# pci-reles.net
KiCad netlist of a schematic drawn in Altium Designer
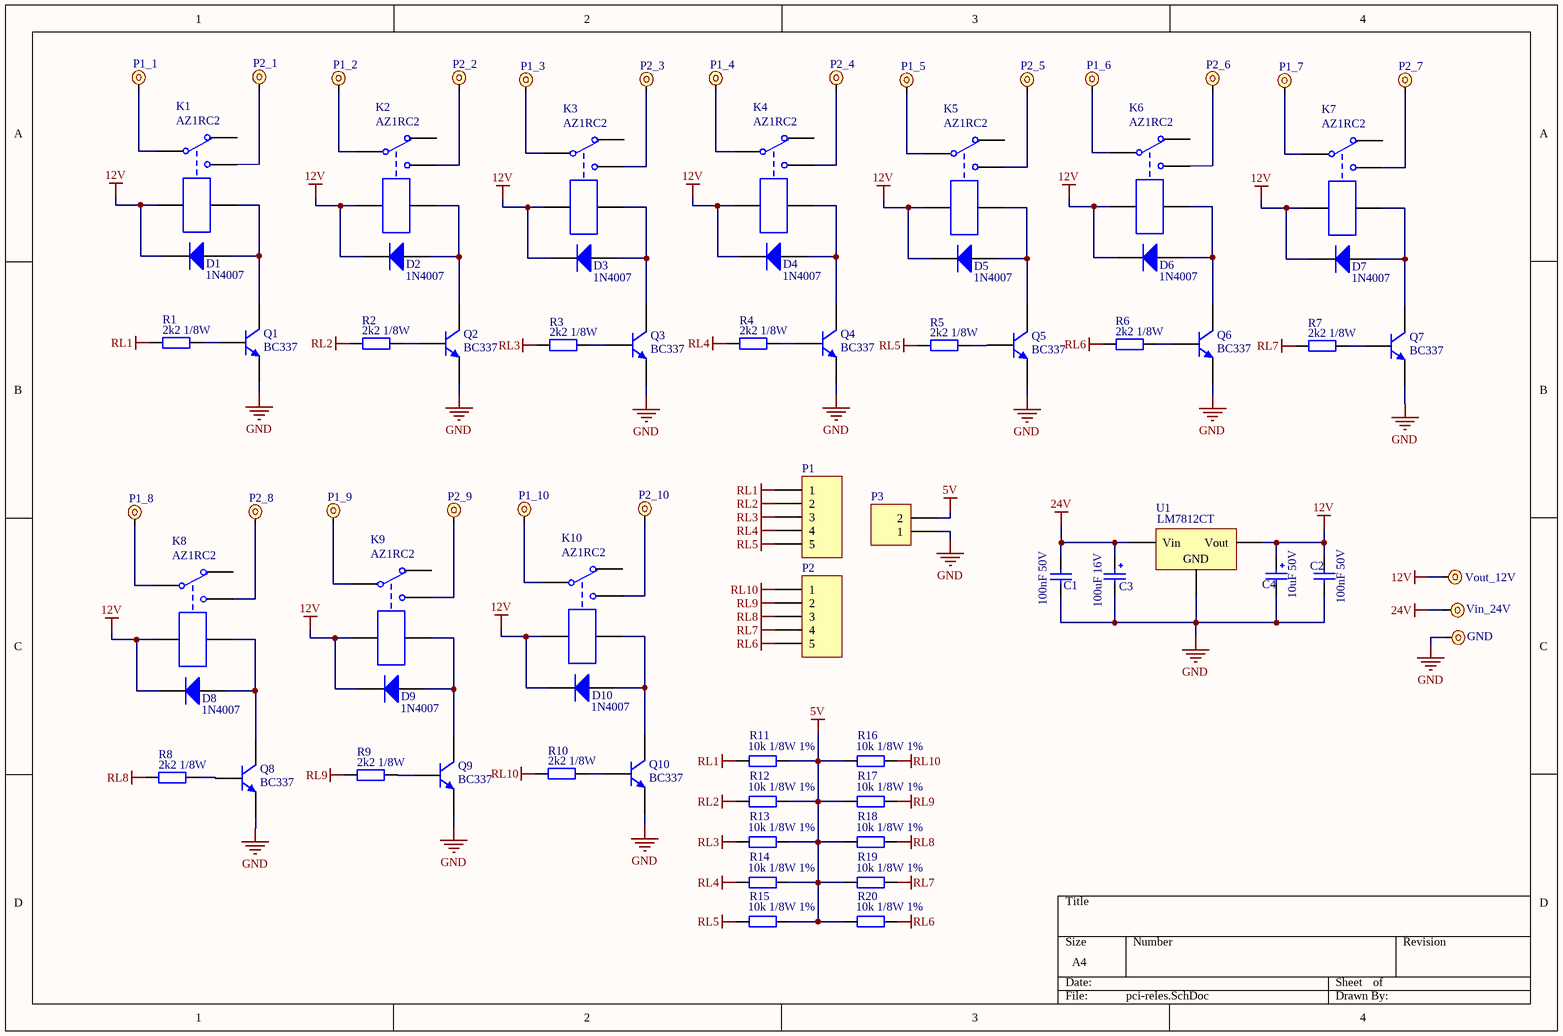
[diagram p0: pci-reles.SchDoc]

(export (version "E")
  (design (tool "Eeschema 10.0.6"))
  (components
    (comp (ref "C1")
      (value "100nF 50V")
      (footprint "Lib PTH:CAP CER 6 x 3 x 5")
      (description "CAP CER 0.1UF 50V Y5V RADIAL")
      (fields
        (field (name "MANUFACTURER") "AVX Corporation")
        (field (name "MANUFACTURER PART NUMBER") "5ZH104ZOCAM")
      )
      (libsource (lib "Lib PTH") (part "Cap Cerâmico 100nF 50V"))
    )
    (comp (ref "C2")
      (value "100nF 50V")
      (footprint "Lib PTH:CAP CER 6 x 3 x 5")
      (description "CAP CER 0.1UF 50V Y5V RADIAL")
      (fields
        (field (name "MANUFACTURER") "AVX Corporation")
        (field (name "MANUFACTURER PART NUMBER") "5ZH104ZOCAM")
      )
      (libsource (lib "Lib PTH") (part "Cap Cerâmico 100nF 50V"))
    )
    (comp (ref "C3")
      (value "100uF 16V")
      (footprint "Lib PTH:CAP ELE 5 x 11 x 2")
      (description "CAP ALUM 100UF 20% 16V RADIAL")
      (fields
        (field (name "MANUFACTURER") "Nichicon")
        (field (name "MANUFACTURER PART NUMBER") "UFW1C101MDD1TD")
      )
      (libsource (lib "Lib PTH") (part "Cap Eletrolitico 100uF/16V"))
    )
    (comp (ref "C4")
      (value "10uF 50V")
      (footprint "Lib PTH:CAP ELE 5 x 11 x 2")
      (description "CAP ALUM 10UF 20% 400V RADIAL")
      (fields
        (field (name "MANUFACTURER") "Nichicon")
        (field (name "MANUFACTURER PART NUMBER") "UVY2G100MPD")
      )
      (libsource (lib "Lib PTH") (part "Cap Eletrolitico 10uF 400V"))
    )
    (comp (ref "D1")
      (value "1N4007")
      (footprint "Lib PTH:DO-41")
      (description "DIODE GEN PURP 1KV 1A DO41")
      (fields
        (field (name "MANUFACTURER") "Diodes Incorporated")
        (field (name "MANUFACTURER PART NUMBER") "1N4007G-T")
      )
      (libsource (lib "Lib PTH") (part "Diodo 1N4007"))
    )
    (comp (ref "D2")
      (value "1N4007")
      (footprint "Lib PTH:DO-41")
      (description "DIODE GEN PURP 1KV 1A DO41")
      (fields
        (field (name "MANUFACTURER") "Diodes Incorporated")
        (field (name "MANUFACTURER PART NUMBER") "1N4007G-T")
      )
      (libsource (lib "Lib PTH") (part "Diodo 1N4007"))
    )
    (comp (ref "D3")
      (value "1N4007")
      (footprint "Lib PTH:DO-41")
      (description "DIODE GEN PURP 1KV 1A DO41")
      (fields
        (field (name "MANUFACTURER") "Diodes Incorporated")
        (field (name "MANUFACTURER PART NUMBER") "1N4007G-T")
      )
      (libsource (lib "Lib PTH") (part "Diodo 1N4007"))
    )
    (comp (ref "D4")
      (value "1N4007")
      (footprint "Lib PTH:DO-41")
      (description "DIODE GEN PURP 1KV 1A DO41")
      (fields
        (field (name "MANUFACTURER") "Diodes Incorporated")
        (field (name "MANUFACTURER PART NUMBER") "1N4007G-T")
      )
      (libsource (lib "Lib PTH") (part "Diodo 1N4007"))
    )
    (comp (ref "D5")
      (value "1N4007")
      (footprint "Lib PTH:DO-41")
      (description "DIODE GEN PURP 1KV 1A DO41")
      (fields
        (field (name "MANUFACTURER") "Diodes Incorporated")
        (field (name "MANUFACTURER PART NUMBER") "1N4007G-T")
      )
      (libsource (lib "Lib PTH") (part "Diodo 1N4007"))
    )
    (comp (ref "D6")
      (value "1N4007")
      (footprint "Lib PTH:DO-41")
      (description "DIODE GEN PURP 1KV 1A DO41")
      (fields
        (field (name "MANUFACTURER") "Diodes Incorporated")
        (field (name "MANUFACTURER PART NUMBER") "1N4007G-T")
      )
      (libsource (lib "Lib PTH") (part "Diodo 1N4007"))
    )
    (comp (ref "D7")
      (value "1N4007")
      (footprint "Lib PTH:DO-41")
      (description "DIODE GEN PURP 1KV 1A DO41")
      (fields
        (field (name "MANUFACTURER") "Diodes Incorporated")
        (field (name "MANUFACTURER PART NUMBER") "1N4007G-T")
      )
      (libsource (lib "Lib PTH") (part "Diodo 1N4007"))
    )
    (comp (ref "D8")
      (value "1N4007")
      (footprint "Lib PTH:DO-41")
      (description "DIODE GEN PURP 1KV 1A DO41")
      (fields
        (field (name "MANUFACTURER") "Diodes Incorporated")
        (field (name "MANUFACTURER PART NUMBER") "1N4007G-T")
      )
      (libsource (lib "Lib PTH") (part "Diodo 1N4007"))
    )
    (comp (ref "D9")
      (value "1N4007")
      (footprint "Lib PTH:DO-41")
      (description "DIODE GEN PURP 1KV 1A DO41")
      (fields
        (field (name "MANUFACTURER") "Diodes Incorporated")
        (field (name "MANUFACTURER PART NUMBER") "1N4007G-T")
      )
      (libsource (lib "Lib PTH") (part "Diodo 1N4007"))
    )
    (comp (ref "D10")
      (value "1N4007")
      (footprint "Lib PTH:DO-41")
      (description "DIODE GEN PURP 1KV 1A DO41")
      (fields
        (field (name "MANUFACTURER") "Diodes Incorporated")
        (field (name "MANUFACTURER PART NUMBER") "1N4007G-T")
      )
      (libsource (lib "Lib PTH") (part "Diodo 1N4007"))
    )
    (comp (ref "GND")
      (value "PAD 1.5x3mm")
      (footprint "Lib PTH:PAD 1.5x3mm")
      (description "PAD")
      (libsource (lib "Lib PTH") (part "PAD 1.5x3mm"))
    )
    (comp (ref "K1")
      (value "AZ1RC2")
      (footprint "Lib PTH:RELE SPDT")
      (description "RELAY GEN PURPOSE SPDT 10A 12V")
      (fields (field (name "MANUFACTURER") "Metaltex"))
      (libsource (lib "Lib PTH") (part "Rele AZ1RC2"))
    )
    (comp (ref "K2")
      (value "AZ1RC2")
      (footprint "Lib PTH:RELE SPDT")
      (description "RELAY GEN PURPOSE SPDT 10A 12V")
      (fields (field (name "MANUFACTURER") "Metaltex"))
      (libsource (lib "Lib PTH") (part "Rele AZ1RC2"))
    )
    (comp (ref "K3")
      (value "AZ1RC2")
      (footprint "Lib PTH:RELE SPDT")
      (description "RELAY GEN PURPOSE SPDT 10A 12V")
      (fields (field (name "MANUFACTURER") "Metaltex"))
      (libsource (lib "Lib PTH") (part "Rele AZ1RC2"))
    )
    (comp (ref "K4")
      (value "AZ1RC2")
      (footprint "Lib PTH:RELE SPDT")
      (description "RELAY GEN PURPOSE SPDT 10A 12V")
      (fields (field (name "MANUFACTURER") "Metaltex"))
      (libsource (lib "Lib PTH") (part "Rele AZ1RC2"))
    )
    (comp (ref "K5")
      (value "AZ1RC2")
      (footprint "Lib PTH:RELE SPDT")
      (description "RELAY GEN PURPOSE SPDT 10A 12V")
      (fields (field (name "MANUFACTURER") "Metaltex"))
      (libsource (lib "Lib PTH") (part "Rele AZ1RC2"))
    )
    (comp (ref "K6")
      (value "AZ1RC2")
      (footprint "Lib PTH:RELE SPDT")
      (description "RELAY GEN PURPOSE SPDT 10A 12V")
      (fields (field (name "MANUFACTURER") "Metaltex"))
      (libsource (lib "Lib PTH") (part "Rele AZ1RC2"))
    )
    (comp (ref "K7")
      (value "AZ1RC2")
      (footprint "Lib PTH:RELE SPDT")
      (description "RELAY GEN PURPOSE SPDT 10A 12V")
      (fields (field (name "MANUFACTURER") "Metaltex"))
      (libsource (lib "Lib PTH") (part "Rele AZ1RC2"))
    )
    (comp (ref "K8")
      (value "AZ1RC2")
      (footprint "Lib PTH:RELE SPDT")
      (description "RELAY GEN PURPOSE SPDT 10A 12V")
      (fields (field (name "MANUFACTURER") "Metaltex"))
      (libsource (lib "Lib PTH") (part "Rele AZ1RC2"))
    )
    (comp (ref "K9")
      (value "AZ1RC2")
      (footprint "Lib PTH:RELE SPDT")
      (description "RELAY GEN PURPOSE SPDT 10A 12V")
      (fields (field (name "MANUFACTURER") "Metaltex"))
      (libsource (lib "Lib PTH") (part "Rele AZ1RC2"))
    )
    (comp (ref "K10")
      (value "AZ1RC2")
      (footprint "Lib PTH:RELE SPDT")
      (description "RELAY GEN PURPOSE SPDT 10A 12V")
      (fields (field (name "MANUFACTURER") "Metaltex"))
      (libsource (lib "Lib PTH") (part "Rele AZ1RC2"))
    )
    (comp (ref "P1")
      (value "Barra de Pinos RL")
      (footprint "Lib PTH:HEADER 5X2.54MM")
      (description "CONN HEADER 5 POS 2.54")
      (fields (field (name "MANUFACTURER") "Metaltex") (field (name "MANUFACTURER PART NUMBER") "BPSC-5"))
      (libsource (lib "Lib PTH") (part "Barra de pinos simples 180°, 5 pinos"))
    )
    (comp (ref "P1_1")
      (value "PAD 1.5x3mm")
      (footprint "Lib PTH:PAD 1.5x3mm")
      (description "PAD")
      (libsource (lib "Lib PTH") (part "PAD 1.5x3mm"))
    )
    (comp (ref "P1_2")
      (value "PAD 1.5x3mm")
      (footprint "Lib PTH:PAD 1.5x3mm")
      (description "PAD")
      (libsource (lib "Lib PTH") (part "PAD 1.5x3mm"))
    )
    (comp (ref "P1_3")
      (value "PAD 1.5x3mm")
      (footprint "Lib PTH:PAD 1.5x3mm")
      (description "PAD")
      (libsource (lib "Lib PTH") (part "PAD 1.5x3mm"))
    )
    (comp (ref "P1_4")
      (value "PAD 1.5x3mm")
      (footprint "Lib PTH:PAD 1.5x3mm")
      (description "PAD")
      (libsource (lib "Lib PTH") (part "PAD 1.5x3mm"))
    )
    (comp (ref "P1_5")
      (value "PAD 1.5x3mm")
      (footprint "Lib PTH:PAD 1.5x3mm")
      (description "PAD")
      (libsource (lib "Lib PTH") (part "PAD 1.5x3mm"))
    )
    (comp (ref "P1_6")
      (value "PAD 1.5x3mm")
      (footprint "Lib PTH:PAD 1.5x3mm")
      (description "PAD")
      (libsource (lib "Lib PTH") (part "PAD 1.5x3mm"))
    )
    (comp (ref "P1_7")
      (value "PAD 1.5x3mm")
      (footprint "Lib PTH:PAD 1.5x3mm")
      (description "PAD")
      (libsource (lib "Lib PTH") (part "PAD 1.5x3mm"))
    )
    (comp (ref "P1_8")
      (value "PAD 1.5x3mm")
      (footprint "Lib PTH:PAD 1.5x3mm")
      (description "PAD")
      (libsource (lib "Lib PTH") (part "PAD 1.5x3mm"))
    )
    (comp (ref "P1_9")
      (value "PAD 1.5x3mm")
      (footprint "Lib PTH:PAD 1.5x3mm")
      (description "PAD")
      (libsource (lib "Lib PTH") (part "PAD 1.5x3mm"))
    )
    (comp (ref "P1_10")
      (value "PAD 1.5x3mm")
      (footprint "Lib PTH:PAD 1.5x3mm")
      (description "PAD")
      (libsource (lib "Lib PTH") (part "PAD 1.5x3mm"))
    )
    (comp (ref "P2")
      (value "Barra de Pinos RL")
      (footprint "Lib PTH:HEADER 5X2.54MM")
      (description "CONN HEADER 5 POS 2.54")
      (fields (field (name "MANUFACTURER") "Metaltex") (field (name "MANUFACTURER PART NUMBER") "BPSC-5"))
      (libsource (lib "Lib PTH") (part "Barra de pinos simples 180°, 5 pinos"))
    )
    (comp (ref "P2_1")
      (value "PAD 1.5x3mm")
      (footprint "Lib PTH:PAD 1.5x3mm")
      (description "PAD")
      (libsource (lib "Lib PTH") (part "PAD 1.5x3mm"))
    )
    (comp (ref "P2_2")
      (value "PAD 1.5x3mm")
      (footprint "Lib PTH:PAD 1.5x3mm")
      (description "PAD")
      (libsource (lib "Lib PTH") (part "PAD 1.5x3mm"))
    )
    (comp (ref "P2_3")
      (value "PAD 1.5x3mm")
      (footprint "Lib PTH:PAD 1.5x3mm")
      (description "PAD")
      (libsource (lib "Lib PTH") (part "PAD 1.5x3mm"))
    )
    (comp (ref "P2_4")
      (value "PAD 1.5x3mm")
      (footprint "Lib PTH:PAD 1.5x3mm")
      (description "PAD")
      (libsource (lib "Lib PTH") (part "PAD 1.5x3mm"))
    )
    (comp (ref "P2_5")
      (value "PAD 1.5x3mm")
      (footprint "Lib PTH:PAD 1.5x3mm")
      (description "PAD")
      (libsource (lib "Lib PTH") (part "PAD 1.5x3mm"))
    )
    (comp (ref "P2_6")
      (value "PAD 1.5x3mm")
      (footprint "Lib PTH:PAD 1.5x3mm")
      (description "PAD")
      (libsource (lib "Lib PTH") (part "PAD 1.5x3mm"))
    )
    (comp (ref "P2_7")
      (value "PAD 1.5x3mm")
      (footprint "Lib PTH:PAD 1.5x3mm")
      (description "PAD")
      (libsource (lib "Lib PTH") (part "PAD 1.5x3mm"))
    )
    (comp (ref "P2_8")
      (value "PAD 1.5x3mm")
      (footprint "Lib PTH:PAD 1.5x3mm")
      (description "PAD")
      (libsource (lib "Lib PTH") (part "PAD 1.5x3mm"))
    )
    (comp (ref "P2_9")
      (value "PAD 1.5x3mm")
      (footprint "Lib PTH:PAD 1.5x3mm")
      (description "PAD")
      (libsource (lib "Lib PTH") (part "PAD 1.5x3mm"))
    )
    (comp (ref "P2_10")
      (value "PAD 1.5x3mm")
      (footprint "Lib PTH:PAD 1.5x3mm")
      (description "PAD")
      (libsource (lib "Lib PTH") (part "PAD 1.5x3mm"))
    )
    (comp (ref "P3")
      (value "Barra de Pinos VCC/GND")
      (footprint "Lib PTH:HEADER 2X2.54MM")
      (description "CONN HEADER 2 POS 2.54")
      (fields (field (name "MANUFACTURER") "Metaltex") (field (name "MANUFACTURER PART NUMBER") "BPSC-2"))
      (libsource (lib "Lib PTH") (part "Barra de pinos simples 180°, 2 pinos"))
    )
    (comp (ref "Q1")
      (value "BC337")
      (footprint "Lib PTH:TO-92A")
      (description "TRANS NPN 45V 0.8A TO-92")
      (fields
        (field (name "MANUFACTURER") "ON Semiconductor")
        (field (name "MANUFACTURER PART NUMBER") "BC33740TA")
      )
      (libsource (lib "Lib PTH") (part "Transistor NPN BC337-40"))
    )
    (comp (ref "Q2")
      (value "BC337")
      (footprint "Lib PTH:TO-92A")
      (description "TRANS NPN 45V 0.8A TO-92")
      (fields
        (field (name "MANUFACTURER") "ON Semiconductor")
        (field (name "MANUFACTURER PART NUMBER") "BC33740TA")
      )
      (libsource (lib "Lib PTH") (part "Transistor NPN BC337-40"))
    )
    (comp (ref "Q3")
      (value "BC337")
      (footprint "Lib PTH:TO-92A")
      (description "TRANS NPN 45V 0.8A TO-92")
      (fields
        (field (name "MANUFACTURER") "ON Semiconductor")
        (field (name "MANUFACTURER PART NUMBER") "BC33740TA")
      )
      (libsource (lib "Lib PTH") (part "Transistor NPN BC337-40"))
    )
    (comp (ref "Q4")
      (value "BC337")
      (footprint "Lib PTH:TO-92A")
      (description "TRANS NPN 45V 0.8A TO-92")
      (fields
        (field (name "MANUFACTURER") "ON Semiconductor")
        (field (name "MANUFACTURER PART NUMBER") "BC33740TA")
      )
      (libsource (lib "Lib PTH") (part "Transistor NPN BC337-40"))
    )
    (comp (ref "Q5")
      (value "BC337")
      (footprint "Lib PTH:TO-92A")
      (description "TRANS NPN 45V 0.8A TO-92")
      (fields
        (field (name "MANUFACTURER") "ON Semiconductor")
        (field (name "MANUFACTURER PART NUMBER") "BC33740TA")
      )
      (libsource (lib "Lib PTH") (part "Transistor NPN BC337-40"))
    )
    (comp (ref "Q6")
      (value "BC337")
      (footprint "Lib PTH:TO-92A")
      (description "TRANS NPN 45V 0.8A TO-92")
      (fields
        (field (name "MANUFACTURER") "ON Semiconductor")
        (field (name "MANUFACTURER PART NUMBER") "BC33740TA")
      )
      (libsource (lib "Lib PTH") (part "Transistor NPN BC337-40"))
    )
    (comp (ref "Q7")
      (value "BC337")
      (footprint "Lib PTH:TO-92A")
      (description "TRANS NPN 45V 0.8A TO-92")
      (fields
        (field (name "MANUFACTURER") "ON Semiconductor")
        (field (name "MANUFACTURER PART NUMBER") "BC33740TA")
      )
      (libsource (lib "Lib PTH") (part "Transistor NPN BC337-40"))
    )
    (comp (ref "Q8")
      (value "BC337")
      (footprint "Lib PTH:TO-92A")
      (description "TRANS NPN 45V 0.8A TO-92")
      (fields
        (field (name "MANUFACTURER") "ON Semiconductor")
        (field (name "MANUFACTURER PART NUMBER") "BC33740TA")
      )
      (libsource (lib "Lib PTH") (part "Transistor NPN BC337-40"))
    )
    (comp (ref "Q9")
      (value "BC337")
      (footprint "Lib PTH:TO-92A")
      (description "TRANS NPN 45V 0.8A TO-92")
      (fields
        (field (name "MANUFACTURER") "ON Semiconductor")
        (field (name "MANUFACTURER PART NUMBER") "BC33740TA")
      )
      (libsource (lib "Lib PTH") (part "Transistor NPN BC337-40"))
    )
    (comp (ref "Q10")
      (value "BC337")
      (footprint "Lib PTH:TO-92A")
      (description "TRANS NPN 45V 0.8A TO-92")
      (fields
        (field (name "MANUFACTURER") "ON Semiconductor")
        (field (name "MANUFACTURER PART NUMBER") "BC33740TA")
      )
      (libsource (lib "Lib PTH") (part "Transistor NPN BC337-40"))
    )
    (comp (ref "R1")
      (value "2k2 1/8W")
      (footprint "Lib PTH:RES CR16")
      (description "RES 2K2 OHM 1/8W 5% AXIAL")
      (fields
        (field (name "MANUFACTURER") "Stackpole Electronics Inc.")
        (field (name "MANUFACTURER PART NUMBER") "CF18JT2K20")
      )
      (libsource (lib "Lib PTH") (part "Res 2k2 1/8W 5% CR16"))
    )
    (comp (ref "R2")
      (value "2k2 1/8W")
      (footprint "Lib PTH:RES CR16")
      (description "RES 2K2 OHM 1/8W 5% AXIAL")
      (fields
        (field (name "MANUFACTURER") "Stackpole Electronics Inc.")
        (field (name "MANUFACTURER PART NUMBER") "CF18JT2K20")
      )
      (libsource (lib "Lib PTH") (part "Res 2k2 1/8W 5% CR16"))
    )
    (comp (ref "R3")
      (value "2k2 1/8W")
      (footprint "Lib PTH:RES CR16")
      (description "RES 2K2 OHM 1/8W 5% AXIAL")
      (fields
        (field (name "MANUFACTURER") "Stackpole Electronics Inc.")
        (field (name "MANUFACTURER PART NUMBER") "CF18JT2K20")
      )
      (libsource (lib "Lib PTH") (part "Res 2k2 1/8W 5% CR16"))
    )
    (comp (ref "R4")
      (value "2k2 1/8W")
      (footprint "Lib PTH:RES CR16")
      (description "RES 2K2 OHM 1/8W 5% AXIAL")
      (fields
        (field (name "MANUFACTURER") "Stackpole Electronics Inc.")
        (field (name "MANUFACTURER PART NUMBER") "CF18JT2K20")
      )
      (libsource (lib "Lib PTH") (part "Res 2k2 1/8W 5% CR16"))
    )
    (comp (ref "R5")
      (value "2k2 1/8W")
      (footprint "Lib PTH:RES CR16")
      (description "RES 2K2 OHM 1/8W 5% AXIAL")
      (fields
        (field (name "MANUFACTURER") "Stackpole Electronics Inc.")
        (field (name "MANUFACTURER PART NUMBER") "CF18JT2K20")
      )
      (libsource (lib "Lib PTH") (part "Res 2k2 1/8W 5% CR16"))
    )
    (comp (ref "R6")
      (value "2k2 1/8W")
      (footprint "Lib PTH:RES CR16")
      (description "RES 2K2 OHM 1/8W 5% AXIAL")
      (fields
        (field (name "MANUFACTURER") "Stackpole Electronics Inc.")
        (field (name "MANUFACTURER PART NUMBER") "CF18JT2K20")
      )
      (libsource (lib "Lib PTH") (part "Res 2k2 1/8W 5% CR16"))
    )
    (comp (ref "R7")
      (value "2k2 1/8W")
      (footprint "Lib PTH:RES CR16")
      (description "RES 2K2 OHM 1/8W 5% AXIAL")
      (fields
        (field (name "MANUFACTURER") "Stackpole Electronics Inc.")
        (field (name "MANUFACTURER PART NUMBER") "CF18JT2K20")
      )
      (libsource (lib "Lib PTH") (part "Res 2k2 1/8W 5% CR16"))
    )
    (comp (ref "R8")
      (value "2k2 1/8W")
      (footprint "Lib PTH:RES CR16")
      (description "RES 2K2 OHM 1/8W 5% AXIAL")
      (fields
        (field (name "MANUFACTURER") "Stackpole Electronics Inc.")
        (field (name "MANUFACTURER PART NUMBER") "CF18JT2K20")
      )
      (libsource (lib "Lib PTH") (part "Res 2k2 1/8W 5% CR16"))
    )
    (comp (ref "R9")
      (value "2k2 1/8W")
      (footprint "Lib PTH:RES CR16")
      (description "RES 2K2 OHM 1/8W 5% AXIAL")
      (fields
        (field (name "MANUFACTURER") "Stackpole Electronics Inc.")
        (field (name "MANUFACTURER PART NUMBER") "CF18JT2K20")
      )
      (libsource (lib "Lib PTH") (part "Res 2k2 1/8W 5% CR16"))
    )
    (comp (ref "R10")
      (value "2k2 1/8W")
      (footprint "Lib PTH:RES CR16")
      (description "RES 2K2 OHM 1/8W 5% AXIAL")
      (fields
        (field (name "MANUFACTURER") "Stackpole Electronics Inc.")
        (field (name "MANUFACTURER PART NUMBER") "CF18JT2K20")
      )
      (libsource (lib "Lib PTH") (part "Res 2k2 1/8W 5% CR16"))
    )
    (comp (ref "R11")
      (value "10k 1/8W 1%")
      (footprint "Lib PTH:RES CR16")
      (description "RES 10K OHM 1/8W 1% AXIAL")
      (fields
        (field (name "MANUFACTURER") "Stackpole Electronics Inc.")
        (field (name "MANUFACTURER PART NUMBER") "RNF18FTD10K0")
      )
      (libsource (lib "Lib PTH") (part "Res 10k 1/8W 1% CR16"))
    )
    (comp (ref "R12")
      (value "10k 1/8W 1%")
      (footprint "Lib PTH:RES CR16")
      (description "RES 10K OHM 1/8W 1% AXIAL")
      (fields
        (field (name "MANUFACTURER") "Stackpole Electronics Inc.")
        (field (name "MANUFACTURER PART NUMBER") "RNF18FTD10K0")
      )
      (libsource (lib "Lib PTH") (part "Res 10k 1/8W 1% CR16"))
    )
    (comp (ref "R13")
      (value "10k 1/8W 1%")
      (footprint "Lib PTH:RES CR16")
      (description "RES 10K OHM 1/8W 1% AXIAL")
      (fields
        (field (name "MANUFACTURER") "Stackpole Electronics Inc.")
        (field (name "MANUFACTURER PART NUMBER") "RNF18FTD10K0")
      )
      (libsource (lib "Lib PTH") (part "Res 10k 1/8W 1% CR16"))
    )
    (comp (ref "R14")
      (value "10k 1/8W 1%")
      (footprint "Lib PTH:RES CR16")
      (description "RES 10K OHM 1/8W 1% AXIAL")
      (fields
        (field (name "MANUFACTURER") "Stackpole Electronics Inc.")
        (field (name "MANUFACTURER PART NUMBER") "RNF18FTD10K0")
      )
      (libsource (lib "Lib PTH") (part "Res 10k 1/8W 1% CR16"))
    )
    (comp (ref "R15")
      (value "10k 1/8W 1%")
      (footprint "Lib PTH:RES CR16")
      (description "RES 10K OHM 1/8W 1% AXIAL")
      (fields
        (field (name "MANUFACTURER") "Stackpole Electronics Inc.")
        (field (name "MANUFACTURER PART NUMBER") "RNF18FTD10K0")
      )
      (libsource (lib "Lib PTH") (part "Res 10k 1/8W 1% CR16"))
    )
    (comp (ref "R16")
      (value "10k 1/8W 1%")
      (footprint "Lib PTH:RES CR16")
      (description "RES 10K OHM 1/8W 1% AXIAL")
      (fields
        (field (name "MANUFACTURER") "Stackpole Electronics Inc.")
        (field (name "MANUFACTURER PART NUMBER") "RNF18FTD10K0")
      )
      (libsource (lib "Lib PTH") (part "Res 10k 1/8W 1% CR16"))
    )
    (comp (ref "R17")
      (value "10k 1/8W 1%")
      (footprint "Lib PTH:RES CR16")
      (description "RES 10K OHM 1/8W 1% AXIAL")
      (fields
        (field (name "MANUFACTURER") "Stackpole Electronics Inc.")
        (field (name "MANUFACTURER PART NUMBER") "RNF18FTD10K0")
      )
      (libsource (lib "Lib PTH") (part "Res 10k 1/8W 1% CR16"))
    )
    (comp (ref "R18")
      (value "10k 1/8W 1%")
      (footprint "Lib PTH:RES CR16")
      (description "RES 10K OHM 1/8W 1% AXIAL")
      (fields
        (field (name "MANUFACTURER") "Stackpole Electronics Inc.")
        (field (name "MANUFACTURER PART NUMBER") "RNF18FTD10K0")
      )
      (libsource (lib "Lib PTH") (part "Res 10k 1/8W 1% CR16"))
    )
    (comp (ref "R19")
      (value "10k 1/8W 1%")
      (footprint "Lib PTH:RES CR16")
      (description "RES 10K OHM 1/8W 1% AXIAL")
      (fields
        (field (name "MANUFACTURER") "Stackpole Electronics Inc.")
        (field (name "MANUFACTURER PART NUMBER") "RNF18FTD10K0")
      )
      (libsource (lib "Lib PTH") (part "Res 10k 1/8W 1% CR16"))
    )
    (comp (ref "R20")
      (value "10k 1/8W 1%")
      (footprint "Lib PTH:RES CR16")
      (description "RES 10K OHM 1/8W 1% AXIAL")
      (fields
        (field (name "MANUFACTURER") "Stackpole Electronics Inc.")
        (field (name "MANUFACTURER PART NUMBER") "RNF18FTD10K0")
      )
      (libsource (lib "Lib PTH") (part "Res 10k 1/8W 1% CR16"))
    )
    (comp (ref "U1")
      (value "LM7812CT")
      (footprint "Lib PTH:TO220_90")
      (description "IC REG LINEAR 5V 1A TO220-3")
      (fields
        (field (name "MANUFACTURER") "Texas Instruments")
        (field (name "MANUFACTURER PART NUMBER") "LM7805CT/NOPB")
      )
      (libsource (lib "Lib PTH") (part "Regulador de tensão LM7805CT"))
    )
    (comp (ref "Vin_24V")
      (value "PAD 1.5x3mm")
      (footprint "Lib PTH:PAD 1.5x3mm")
      (description "PAD")
      (libsource (lib "Lib PTH") (part "PAD 1.5x3mm"))
    )
    (comp (ref "Vout_12V")
      (value "PAD 1.5x3mm")
      (footprint "Lib PTH:PAD 1.5x3mm")
      (description "PAD")
      (libsource (lib "Lib PTH") (part "PAD 1.5x3mm"))
    )
  )
  (nets
    (net (code "1") (name "5V") (class "Default")
      (node (ref "P3") (pin "2") (pinfunction "2_2") (pintype "passive"))
      (node (ref "R11") (pin "2") (pinfunction "2_2") (pintype "passive"))
      (node (ref "R12") (pin "2") (pinfunction "2_2") (pintype "passive"))
      (node (ref "R13") (pin "2") (pinfunction "2_2") (pintype "passive"))
      (node (ref "R14") (pin "2") (pinfunction "2_2") (pintype "passive"))
      (node (ref "R15") (pin "2") (pinfunction "2_2") (pintype "passive"))
      (node (ref "R16") (pin "1") (pinfunction "1_1") (pintype "passive"))
      (node (ref "R17") (pin "1") (pinfunction "1_1") (pintype "passive"))
      (node (ref "R18") (pin "1") (pinfunction "1_1") (pintype "passive"))
      (node (ref "R19") (pin "1") (pinfunction "1_1") (pintype "passive"))
      (node (ref "R20") (pin "1") (pinfunction "1_1") (pintype "passive"))
    )
    (net (code "2") (name "12V") (class "Default")
      (node (ref "C2") (pin "2") (pinfunction "2_2") (pintype "passive"))
      (node (ref "C4") (pin "1") (pinfunction "1_1") (pintype "passive"))
      (node (ref "D1") (pin "2") (pinfunction "K_2") (pintype "passive"))
      (node (ref "D10") (pin "2") (pinfunction "K_2") (pintype "passive"))
      (node (ref "D2") (pin "2") (pinfunction "K_2") (pintype "passive"))
      (node (ref "D3") (pin "2") (pinfunction "K_2") (pintype "passive"))
      (node (ref "D4") (pin "2") (pinfunction "K_2") (pintype "passive"))
      (node (ref "D5") (pin "2") (pinfunction "K_2") (pintype "passive"))
      (node (ref "D6") (pin "2") (pinfunction "K_2") (pintype "passive"))
      (node (ref "D7") (pin "2") (pinfunction "K_2") (pintype "passive"))
      (node (ref "D8") (pin "2") (pinfunction "K_2") (pintype "passive"))
      (node (ref "D9") (pin "2") (pinfunction "K_2") (pintype "passive"))
      (node (ref "K1") (pin "4") (pinfunction "4_4") (pintype "passive"))
      (node (ref "K10") (pin "4") (pinfunction "4_4") (pintype "passive"))
      (node (ref "K2") (pin "4") (pinfunction "4_4") (pintype "passive"))
      (node (ref "K3") (pin "4") (pinfunction "4_4") (pintype "passive"))
      (node (ref "K4") (pin "4") (pinfunction "4_4") (pintype "passive"))
      (node (ref "K5") (pin "4") (pinfunction "4_4") (pintype "passive"))
      (node (ref "K6") (pin "4") (pinfunction "4_4") (pintype "passive"))
      (node (ref "K7") (pin "4") (pinfunction "4_4") (pintype "passive"))
      (node (ref "K8") (pin "4") (pinfunction "4_4") (pintype "passive"))
      (node (ref "K9") (pin "4") (pinfunction "4_4") (pintype "passive"))
      (node (ref "U1") (pin "3") (pinfunction "Vout_3") (pintype "passive"))
      (node (ref "Vout_12V") (pin "1") (pinfunction "1_1") (pintype "passive"))
    )
    (net (code "3") (name "24V") (class "Default")
      (node (ref "C1") (pin "2") (pinfunction "2_2") (pintype "passive"))
      (node (ref "C3") (pin "1") (pinfunction "1_1") (pintype "passive"))
      (node (ref "U1") (pin "1") (pinfunction "Vin_1") (pintype "passive"))
      (node (ref "Vin_24V") (pin "1") (pinfunction "1_1") (pintype "passive"))
    )
    (net (code "4") (name "GND") (class "Default")
      (node (ref "C1") (pin "1") (pinfunction "1_1") (pintype "passive"))
      (node (ref "C2") (pin "1") (pinfunction "1_1") (pintype "passive"))
      (node (ref "C3") (pin "2") (pinfunction "2_2") (pintype "passive"))
      (node (ref "C4") (pin "2") (pinfunction "2_2") (pintype "passive"))
      (node (ref "GND") (pin "1") (pinfunction "1_1") (pintype "passive"))
      (node (ref "P3") (pin "1") (pinfunction "1_1") (pintype "passive"))
      (node (ref "Q1") (pin "3") (pinfunction "E_3") (pintype "passive"))
      (node (ref "Q10") (pin "3") (pinfunction "E_3") (pintype "passive"))
      (node (ref "Q2") (pin "3") (pinfunction "E_3") (pintype "passive"))
      (node (ref "Q3") (pin "3") (pinfunction "E_3") (pintype "passive"))
      (node (ref "Q4") (pin "3") (pinfunction "E_3") (pintype "passive"))
      (node (ref "Q5") (pin "3") (pinfunction "E_3") (pintype "passive"))
      (node (ref "Q6") (pin "3") (pinfunction "E_3") (pintype "passive"))
      (node (ref "Q7") (pin "3") (pinfunction "E_3") (pintype "passive"))
      (node (ref "Q8") (pin "3") (pinfunction "E_3") (pintype "passive"))
      (node (ref "Q9") (pin "3") (pinfunction "E_3") (pintype "passive"))
      (node (ref "U1") (pin "2") (pinfunction "GND_2") (pintype "passive"))
    )
    (net (code "5") (name "Net-(D1-A)") (class "Default")
      (node (ref "D1") (pin "1") (pinfunction "A_1") (pintype "passive"))
      (node (ref "K1") (pin "5") (pinfunction "5_5") (pintype "passive"))
      (node (ref "Q1") (pin "1") (pinfunction "C_1") (pintype "passive"))
    )
    (net (code "6") (name "Net-(D2-A)") (class "Default")
      (node (ref "D2") (pin "1") (pinfunction "A_1") (pintype "passive"))
      (node (ref "K2") (pin "5") (pinfunction "5_5") (pintype "passive"))
      (node (ref "Q2") (pin "1") (pinfunction "C_1") (pintype "passive"))
    )
    (net (code "7") (name "Net-(D3-A)") (class "Default")
      (node (ref "D3") (pin "1") (pinfunction "A_1") (pintype "passive"))
      (node (ref "K3") (pin "5") (pinfunction "5_5") (pintype "passive"))
      (node (ref "Q3") (pin "1") (pinfunction "C_1") (pintype "passive"))
    )
    (net (code "8") (name "Net-(D4-A)") (class "Default")
      (node (ref "D4") (pin "1") (pinfunction "A_1") (pintype "passive"))
      (node (ref "K4") (pin "5") (pinfunction "5_5") (pintype "passive"))
      (node (ref "Q4") (pin "1") (pinfunction "C_1") (pintype "passive"))
    )
    (net (code "9") (name "Net-(D5-A)") (class "Default")
      (node (ref "D5") (pin "1") (pinfunction "A_1") (pintype "passive"))
      (node (ref "K5") (pin "5") (pinfunction "5_5") (pintype "passive"))
      (node (ref "Q5") (pin "1") (pinfunction "C_1") (pintype "passive"))
    )
    (net (code "10") (name "Net-(D6-A)") (class "Default")
      (node (ref "D6") (pin "1") (pinfunction "A_1") (pintype "passive"))
      (node (ref "K6") (pin "5") (pinfunction "5_5") (pintype "passive"))
      (node (ref "Q6") (pin "1") (pinfunction "C_1") (pintype "passive"))
    )
    (net (code "11") (name "Net-(D7-A)") (class "Default")
      (node (ref "D7") (pin "1") (pinfunction "A_1") (pintype "passive"))
      (node (ref "K7") (pin "5") (pinfunction "5_5") (pintype "passive"))
      (node (ref "Q7") (pin "1") (pinfunction "C_1") (pintype "passive"))
    )
    (net (code "12") (name "Net-(D8-A)") (class "Default")
      (node (ref "D8") (pin "1") (pinfunction "A_1") (pintype "passive"))
      (node (ref "K8") (pin "5") (pinfunction "5_5") (pintype "passive"))
      (node (ref "Q8") (pin "1") (pinfunction "C_1") (pintype "passive"))
    )
    (net (code "13") (name "Net-(D9-A)") (class "Default")
      (node (ref "D9") (pin "1") (pinfunction "A_1") (pintype "passive"))
      (node (ref "K9") (pin "5") (pinfunction "5_5") (pintype "passive"))
      (node (ref "Q9") (pin "1") (pinfunction "C_1") (pintype "passive"))
    )
    (net (code "14") (name "Net-(D10-A)") (class "Default")
      (node (ref "D10") (pin "1") (pinfunction "A_1") (pintype "passive"))
      (node (ref "K10") (pin "5") (pinfunction "5_5") (pintype "passive"))
      (node (ref "Q10") (pin "1") (pinfunction "C_1") (pintype "passive"))
    )
    (net (code "15") (name "Net-(K1-Comum)") (class "Default")
      (node (ref "K1") (pin "1") (pinfunction "Comum_1") (pintype "passive"))
      (node (ref "P1_1") (pin "1") (pinfunction "1_1") (pintype "passive"))
    )
    (net (code "16") (name "Net-(K1-N.A.)") (class "Default")
      (node (ref "K1") (pin "2") (pinfunction "N.A._2") (pintype "passive"))
      (node (ref "P2_1") (pin "1") (pinfunction "1_1") (pintype "passive"))
    )
    (net (code "17") (name "Net-(K2-Comum)") (class "Default")
      (node (ref "K2") (pin "1") (pinfunction "Comum_1") (pintype "passive"))
      (node (ref "P1_2") (pin "1") (pinfunction "1_1") (pintype "passive"))
    )
    (net (code "18") (name "Net-(K2-N.A.)") (class "Default")
      (node (ref "K2") (pin "2") (pinfunction "N.A._2") (pintype "passive"))
      (node (ref "P2_2") (pin "1") (pinfunction "1_1") (pintype "passive"))
    )
    (net (code "19") (name "Net-(K3-Comum)") (class "Default")
      (node (ref "K3") (pin "1") (pinfunction "Comum_1") (pintype "passive"))
      (node (ref "P1_3") (pin "1") (pinfunction "1_1") (pintype "passive"))
    )
    (net (code "20") (name "Net-(K3-N.A.)") (class "Default")
      (node (ref "K3") (pin "2") (pinfunction "N.A._2") (pintype "passive"))
      (node (ref "P2_3") (pin "1") (pinfunction "1_1") (pintype "passive"))
    )
    (net (code "21") (name "Net-(K4-Comum)") (class "Default")
      (node (ref "K4") (pin "1") (pinfunction "Comum_1") (pintype "passive"))
      (node (ref "P1_4") (pin "1") (pinfunction "1_1") (pintype "passive"))
    )
    (net (code "22") (name "Net-(K4-N.A.)") (class "Default")
      (node (ref "K4") (pin "2") (pinfunction "N.A._2") (pintype "passive"))
      (node (ref "P2_4") (pin "1") (pinfunction "1_1") (pintype "passive"))
    )
    (net (code "23") (name "Net-(K5-Comum)") (class "Default")
      (node (ref "K5") (pin "1") (pinfunction "Comum_1") (pintype "passive"))
      (node (ref "P1_5") (pin "1") (pinfunction "1_1") (pintype "passive"))
    )
    (net (code "24") (name "Net-(K5-N.A.)") (class "Default")
      (node (ref "K5") (pin "2") (pinfunction "N.A._2") (pintype "passive"))
      (node (ref "P2_5") (pin "1") (pinfunction "1_1") (pintype "passive"))
    )
    (net (code "25") (name "Net-(K6-Comum)") (class "Default")
      (node (ref "K6") (pin "1") (pinfunction "Comum_1") (pintype "passive"))
      (node (ref "P1_6") (pin "1") (pinfunction "1_1") (pintype "passive"))
    )
    (net (code "26") (name "Net-(K6-N.A.)") (class "Default")
      (node (ref "K6") (pin "2") (pinfunction "N.A._2") (pintype "passive"))
      (node (ref "P2_6") (pin "1") (pinfunction "1_1") (pintype "passive"))
    )
    (net (code "27") (name "Net-(K7-Comum)") (class "Default")
      (node (ref "K7") (pin "1") (pinfunction "Comum_1") (pintype "passive"))
      (node (ref "P1_7") (pin "1") (pinfunction "1_1") (pintype "passive"))
    )
    (net (code "28") (name "Net-(K7-N.A.)") (class "Default")
      (node (ref "K7") (pin "2") (pinfunction "N.A._2") (pintype "passive"))
      (node (ref "P2_7") (pin "1") (pinfunction "1_1") (pintype "passive"))
    )
    (net (code "29") (name "Net-(K8-Comum)") (class "Default")
      (node (ref "K8") (pin "1") (pinfunction "Comum_1") (pintype "passive"))
      (node (ref "P1_8") (pin "1") (pinfunction "1_1") (pintype "passive"))
    )
    (net (code "30") (name "Net-(K8-N.A.)") (class "Default")
      (node (ref "K8") (pin "2") (pinfunction "N.A._2") (pintype "passive"))
      (node (ref "P2_8") (pin "1") (pinfunction "1_1") (pintype "passive"))
    )
    (net (code "31") (name "Net-(K9-Comum)") (class "Default")
      (node (ref "K9") (pin "1") (pinfunction "Comum_1") (pintype "passive"))
      (node (ref "P1_9") (pin "1") (pinfunction "1_1") (pintype "passive"))
    )
    (net (code "32") (name "Net-(K9-N.A.)") (class "Default")
      (node (ref "K9") (pin "2") (pinfunction "N.A._2") (pintype "passive"))
      (node (ref "P2_9") (pin "1") (pinfunction "1_1") (pintype "passive"))
    )
    (net (code "33") (name "Net-(K10-Comum)") (class "Default")
      (node (ref "K10") (pin "1") (pinfunction "Comum_1") (pintype "passive"))
      (node (ref "P1_10") (pin "1") (pinfunction "1_1") (pintype "passive"))
    )
    (net (code "34") (name "Net-(K10-N.A.)") (class "Default")
      (node (ref "K10") (pin "2") (pinfunction "N.A._2") (pintype "passive"))
      (node (ref "P2_10") (pin "1") (pinfunction "1_1") (pintype "passive"))
    )
    (net (code "35") (name "Net-(Q1-B)") (class "Default")
      (node (ref "Q1") (pin "2") (pinfunction "B_2") (pintype "passive"))
      (node (ref "R1") (pin "2") (pinfunction "2_2") (pintype "passive"))
    )
    (net (code "36") (name "Net-(Q2-B)") (class "Default")
      (node (ref "Q2") (pin "2") (pinfunction "B_2") (pintype "passive"))
      (node (ref "R2") (pin "2") (pinfunction "2_2") (pintype "passive"))
    )
    (net (code "37") (name "Net-(Q3-B)") (class "Default")
      (node (ref "Q3") (pin "2") (pinfunction "B_2") (pintype "passive"))
      (node (ref "R3") (pin "2") (pinfunction "2_2") (pintype "passive"))
    )
    (net (code "38") (name "Net-(Q4-B)") (class "Default")
      (node (ref "Q4") (pin "2") (pinfunction "B_2") (pintype "passive"))
      (node (ref "R4") (pin "2") (pinfunction "2_2") (pintype "passive"))
    )
    (net (code "39") (name "Net-(Q5-B)") (class "Default")
      (node (ref "Q5") (pin "2") (pinfunction "B_2") (pintype "passive"))
      (node (ref "R5") (pin "2") (pinfunction "2_2") (pintype "passive"))
    )
    (net (code "40") (name "Net-(Q6-B)") (class "Default")
      (node (ref "Q6") (pin "2") (pinfunction "B_2") (pintype "passive"))
      (node (ref "R6") (pin "2") (pinfunction "2_2") (pintype "passive"))
    )
    (net (code "41") (name "Net-(Q7-B)") (class "Default")
      (node (ref "Q7") (pin "2") (pinfunction "B_2") (pintype "passive"))
      (node (ref "R7") (pin "2") (pinfunction "2_2") (pintype "passive"))
    )
    (net (code "42") (name "Net-(Q8-B)") (class "Default")
      (node (ref "Q8") (pin "2") (pinfunction "B_2") (pintype "passive"))
      (node (ref "R8") (pin "2") (pinfunction "2_2") (pintype "passive"))
    )
    (net (code "43") (name "Net-(Q9-B)") (class "Default")
      (node (ref "Q9") (pin "2") (pinfunction "B_2") (pintype "passive"))
      (node (ref "R9") (pin "2") (pinfunction "2_2") (pintype "passive"))
    )
    (net (code "44") (name "Net-(Q10-B)") (class "Default")
      (node (ref "Q10") (pin "2") (pinfunction "B_2") (pintype "passive"))
      (node (ref "R10") (pin "2") (pinfunction "2_2") (pintype "passive"))
    )
    (net (code "45") (name "RL1") (class "Default")
      (node (ref "P1") (pin "1") (pinfunction "1_1") (pintype "passive"))
      (node (ref "R1") (pin "1") (pinfunction "1_1") (pintype "passive"))
      (node (ref "R11") (pin "1") (pinfunction "1_1") (pintype "passive"))
    )
    (net (code "46") (name "RL2") (class "Default")
      (node (ref "P1") (pin "2") (pinfunction "2_2") (pintype "passive"))
      (node (ref "R12") (pin "1") (pinfunction "1_1") (pintype "passive"))
      (node (ref "R2") (pin "1") (pinfunction "1_1") (pintype "passive"))
    )
    (net (code "47") (name "RL3") (class "Default")
      (node (ref "P1") (pin "3") (pinfunction "3_3") (pintype "passive"))
      (node (ref "R13") (pin "1") (pinfunction "1_1") (pintype "passive"))
      (node (ref "R3") (pin "1") (pinfunction "1_1") (pintype "passive"))
    )
    (net (code "48") (name "RL4") (class "Default")
      (node (ref "P1") (pin "4") (pinfunction "4_4") (pintype "passive"))
      (node (ref "R14") (pin "1") (pinfunction "1_1") (pintype "passive"))
      (node (ref "R4") (pin "1") (pinfunction "1_1") (pintype "passive"))
    )
    (net (code "49") (name "RL5") (class "Default")
      (node (ref "P1") (pin "5") (pinfunction "5_5") (pintype "passive"))
      (node (ref "R15") (pin "1") (pinfunction "1_1") (pintype "passive"))
      (node (ref "R5") (pin "1") (pinfunction "1_1") (pintype "passive"))
    )
    (net (code "50") (name "RL6") (class "Default")
      (node (ref "P2") (pin "5") (pinfunction "5_5") (pintype "passive"))
      (node (ref "R20") (pin "2") (pinfunction "2_2") (pintype "passive"))
      (node (ref "R6") (pin "1") (pinfunction "1_1") (pintype "passive"))
    )
    (net (code "51") (name "RL7") (class "Default")
      (node (ref "P2") (pin "4") (pinfunction "4_4") (pintype "passive"))
      (node (ref "R19") (pin "2") (pinfunction "2_2") (pintype "passive"))
      (node (ref "R7") (pin "1") (pinfunction "1_1") (pintype "passive"))
    )
    (net (code "52") (name "RL8") (class "Default")
      (node (ref "P2") (pin "3") (pinfunction "3_3") (pintype "passive"))
      (node (ref "R18") (pin "2") (pinfunction "2_2") (pintype "passive"))
      (node (ref "R8") (pin "1") (pinfunction "1_1") (pintype "passive"))
    )
    (net (code "53") (name "RL9") (class "Default")
      (node (ref "P2") (pin "2") (pinfunction "2_2") (pintype "passive"))
      (node (ref "R17") (pin "2") (pinfunction "2_2") (pintype "passive"))
      (node (ref "R9") (pin "1") (pinfunction "1_1") (pintype "passive"))
    )
    (net (code "54") (name "RL10") (class "Default")
      (node (ref "P2") (pin "1") (pinfunction "1_1") (pintype "passive"))
      (node (ref "R10") (pin "1") (pinfunction "1_1") (pintype "passive"))
      (node (ref "R16") (pin "2") (pinfunction "2_2") (pintype "passive"))
    )
    (net (code "55") (name "unconnected-(K1-N.F.-Pad3)") (class "Default")
      (node (ref "K1") (pin "3") (pinfunction "N.F._3") (pintype "passive"))
    )
    (net (code "56") (name "unconnected-(K2-N.F.-Pad3)") (class "Default")
      (node (ref "K2") (pin "3") (pinfunction "N.F._3") (pintype "passive"))
    )
    (net (code "57") (name "unconnected-(K3-N.F.-Pad3)") (class "Default")
      (node (ref "K3") (pin "3") (pinfunction "N.F._3") (pintype "passive"))
    )
    (net (code "58") (name "unconnected-(K4-N.F.-Pad3)") (class "Default")
      (node (ref "K4") (pin "3") (pinfunction "N.F._3") (pintype "passive"))
    )
    (net (code "59") (name "unconnected-(K5-N.F.-Pad3)") (class "Default")
      (node (ref "K5") (pin "3") (pinfunction "N.F._3") (pintype "passive"))
    )
    (net (code "60") (name "unconnected-(K6-N.F.-Pad3)") (class "Default")
      (node (ref "K6") (pin "3") (pinfunction "N.F._3") (pintype "passive"))
    )
    (net (code "61") (name "unconnected-(K7-N.F.-Pad3)") (class "Default")
      (node (ref "K7") (pin "3") (pinfunction "N.F._3") (pintype "passive"))
    )
    (net (code "62") (name "unconnected-(K8-N.F.-Pad3)") (class "Default")
      (node (ref "K8") (pin "3") (pinfunction "N.F._3") (pintype "passive"))
    )
    (net (code "63") (name "unconnected-(K9-N.F.-Pad3)") (class "Default")
      (node (ref "K9") (pin "3") (pinfunction "N.F._3") (pintype "passive"))
    )
    (net (code "64") (name "unconnected-(K10-N.F.-Pad3)") (class "Default")
      (node (ref "K10") (pin "3") (pinfunction "N.F._3") (pintype "passive"))
    )
  )
)
